# ETAG.net
KiCad netlist of a schematic drawn in EAGLE
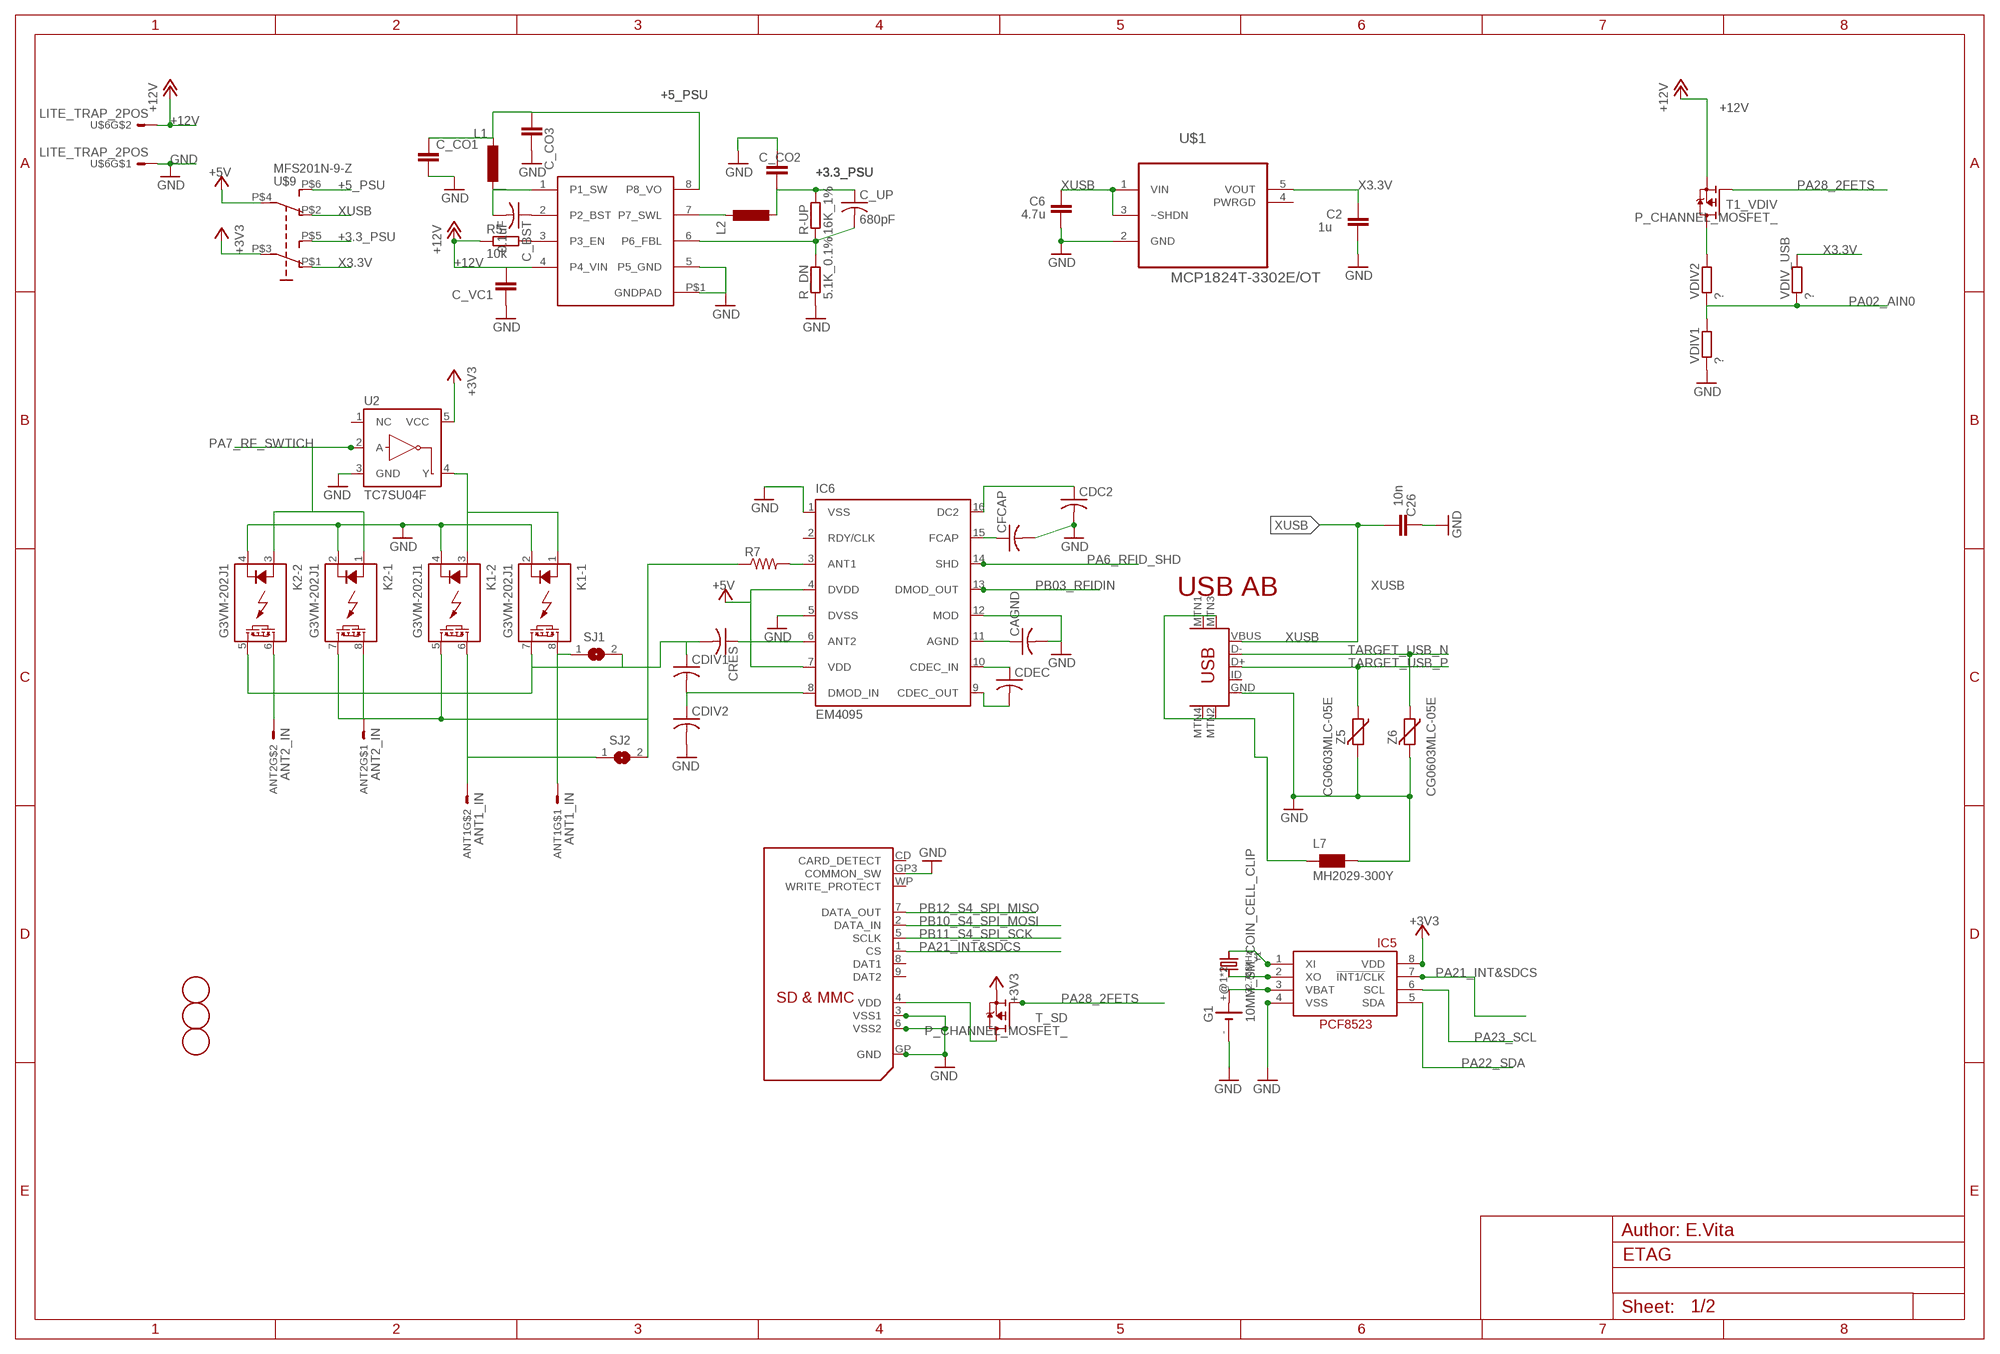
[diagram p0: schematic, sheet 1]
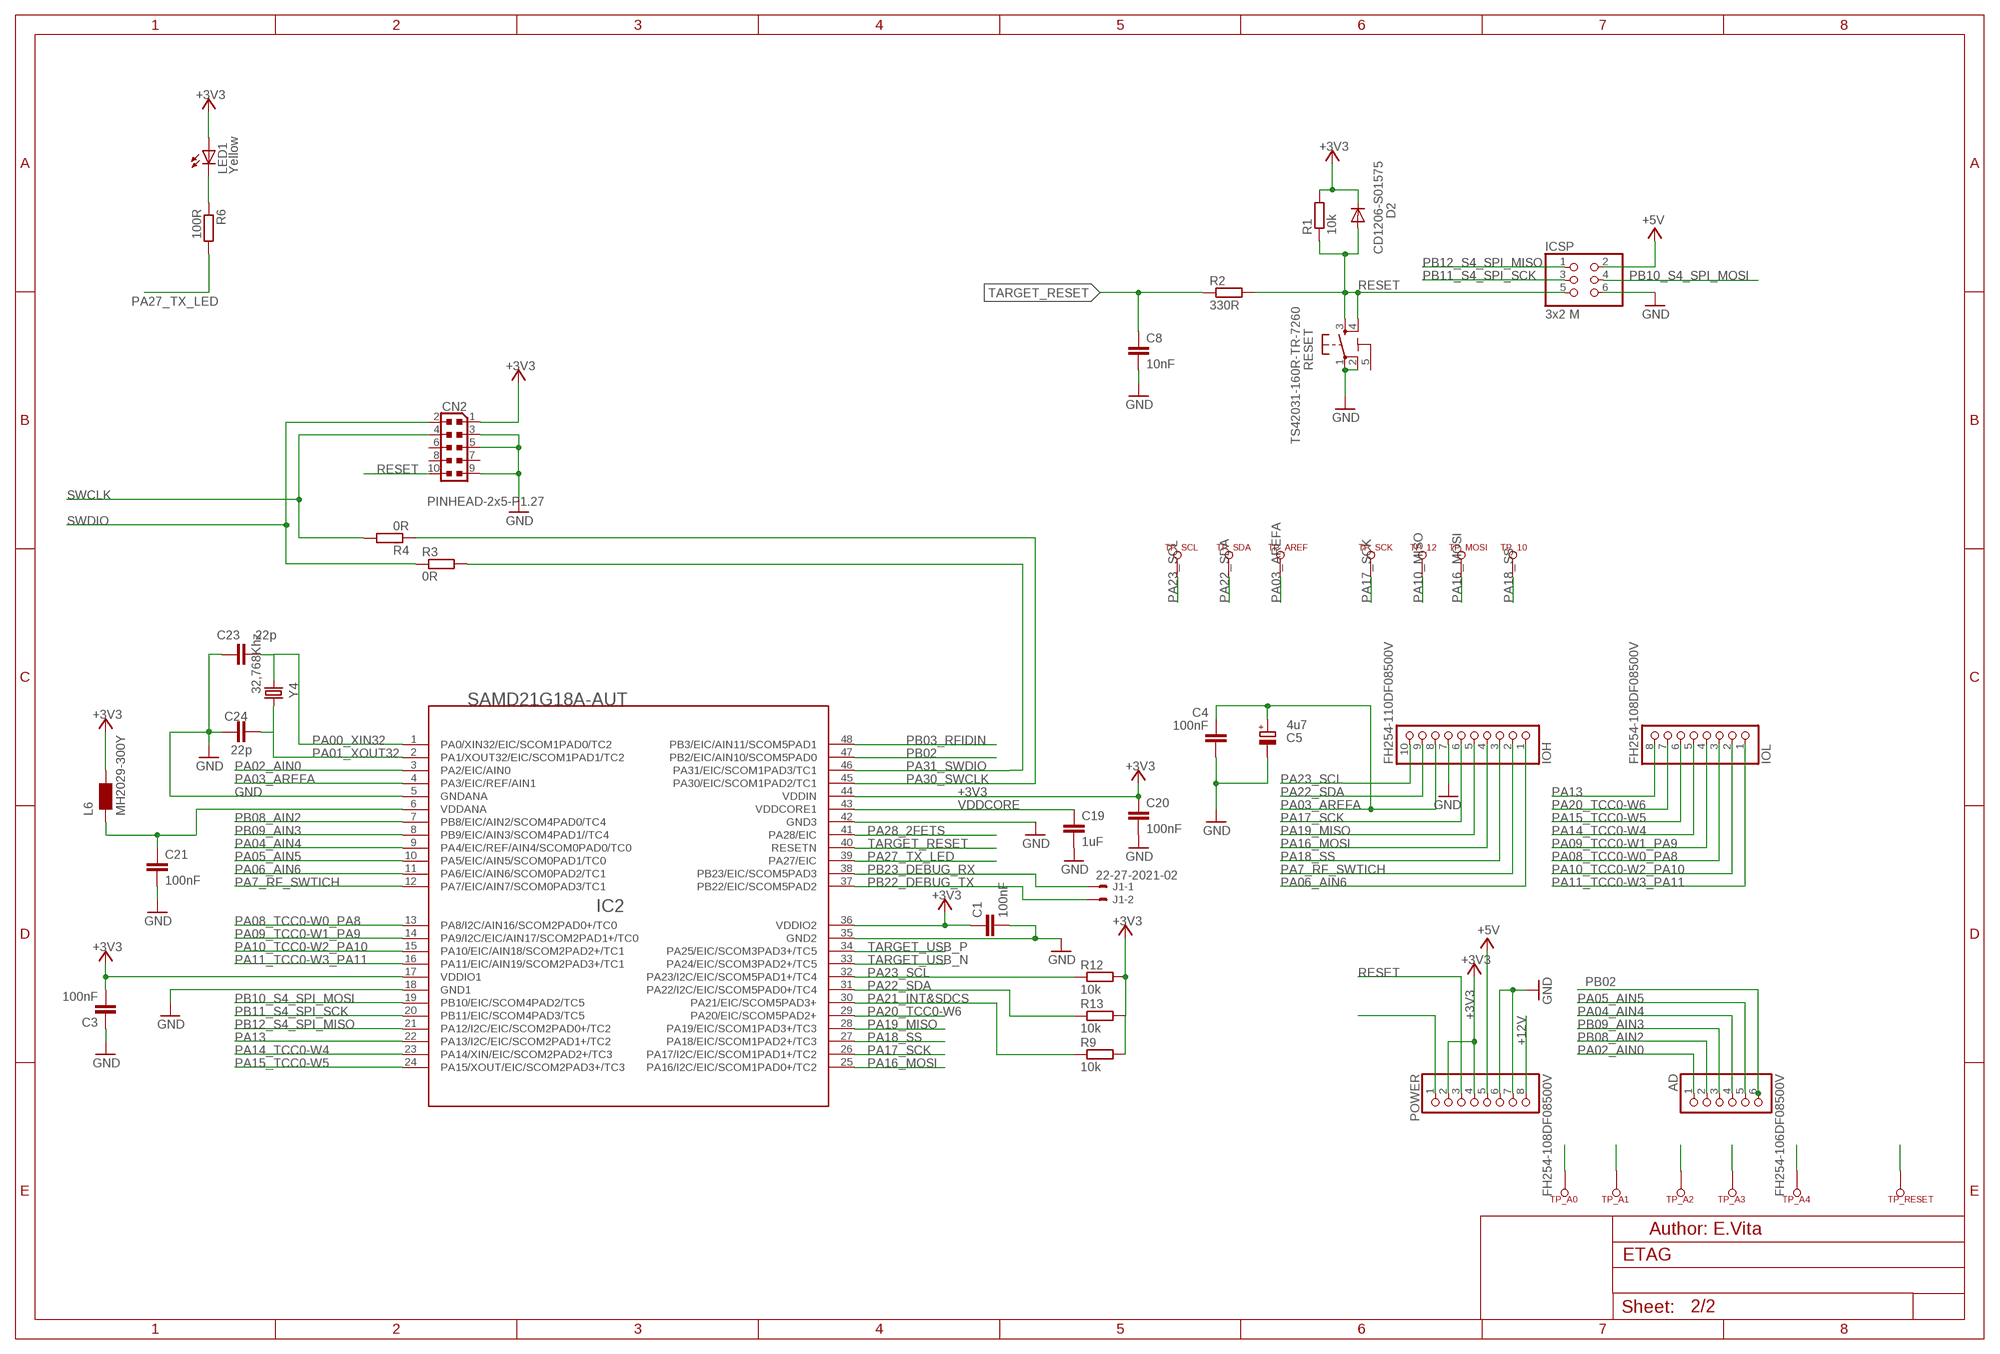
[diagram p1: schematic, sheet 2]

(export (version "E")
  (design (tool "Eeschema 10.0.6"))
  (components
    (comp (ref "AD")
      (value "FH254-106DF08500V")
      (footprint "eagle-import:1X06")
      (fields (field (name "PART_NUMBER") "20TW-535"))
      (libsource (lib "eagle-import") (part "1682_20TW-535_STD"))
    )
    (comp (ref "C1")
      (value "100nF")
      (footprint "eagle-import:C0603-ROUND")
      (fields (field (name "PART_NUMBER") "cl10b104kbnc"))
      (libsource (lib "eagle-import") (part "0015_100NF_0603"))
    )
    (comp (ref "C3")
      (value "100nF")
      (footprint "eagle-import:C0603-ROUND")
      (fields (field (name "PART_NUMBER") "cl10b104kbnc"))
      (libsource (lib "eagle-import") (part "0015_100NF_0603"))
    )
    (comp (ref "C4")
      (value "100nF")
      (footprint "eagle-import:C0603-ROUND")
      (fields (field (name "PART_NUMBER") "cl10b104kbnc"))
      (libsource (lib "eagle-import") (part "0015_100NF_0603"))
    )
    (comp (ref "C5")
      (value "4u7")
      (footprint "eagle-import:SMC_A")
      (fields (field (name "PART_NUMBER") "TAJA475M016RNJ"))
      (libsource (lib "eagle-import") (part "0474_TAJA475M016RNJ"))
    )
    (comp (ref "C8")
      (value "10nF")
      (footprint "eagle-import:C0603-ROUND")
      (fields (field (name "PART_NUMBER") "10nF_0603"))
      (libsource (lib "eagle-import") (part "0142_10NF_0603"))
    )
    (comp (ref "C19")
      (value "1uF")
      (footprint "eagle-import:C0603-ROUND")
      (fields (field (name "PART_NUMBER") "1uF_0603/GRM188R61E105KA12D"))
      (libsource (lib "eagle-import") (part "0006_1UF_0603/GRM188R61E105KA12D"))
    )
    (comp (ref "C20")
      (value "100nF")
      (footprint "eagle-import:C0603-ROUND")
      (fields (field (name "PART_NUMBER") "cl10b104kbnc"))
      (libsource (lib "eagle-import") (part "0015_100NF_0603"))
    )
    (comp (ref "C21")
      (value "100nF")
      (footprint "eagle-import:C0603-ROUND")
      (fields (field (name "PART_NUMBER") "cl10b104kbnc"))
      (libsource (lib "eagle-import") (part "0015_100NF_0603"))
    )
    (comp (ref "C23")
      (value "22p")
      (footprint "eagle-import:C0603-ROUND")
      (fields (field (name "PART_NUMBER") "22pF_0603"))
      (libsource (lib "eagle-import") (part "0014_22PF_0603"))
    )
    (comp (ref "C24")
      (value "22p")
      (footprint "eagle-import:C0603-ROUND")
      (fields (field (name "PART_NUMBER") "22pF_0603"))
      (libsource (lib "eagle-import") (part "0014_22PF_0603"))
    )
    (comp (ref "CN2")
      (value "PINHEAD-2x5-P1.27")
      (footprint "eagle-import:PINHEAD_2X05_127")
      (libsource (lib "eagle-import") (part "0171_PH127-205DF055G00AROUND-PADS"))
    )
    (comp (ref "D2")
      (value "CD1206-S01575")
      (footprint "eagle-import:MINIMELF")
      (libsource (lib "eagle-import") (part "0012_CD1206-S01575"))
    )
    (comp (ref "IC2")
      (value "SAMD21G18A-AUT")
      (footprint "eagle-import:TQFP48-7X7")
      (libsource (lib "eagle-import") (part "1792_SAMD21G18A-AUT"))
    )
    (comp (ref "ICSP")
      (value "3x2 M")
      (footprint "eagle-import:2X03")
      (fields (field (name "PART_NUMBER") "PH254-203DF118A00V"))
      (libsource (lib "eagle-import") (part "0114_PH254-203DF118A00V"))
    )
    (comp (ref "IOH")
      (value "FH254-110DF08500V")
      (footprint "eagle-import:1X10")
      (fields (field (name "PART_NUMBER") "20TW-537"))
      (libsource (lib "eagle-import") (part "1684_20TW-537"))
    )
    (comp (ref "IOL")
      (value "FH254-108DF08500V")
      (footprint "eagle-import:1X08")
      (fields (field (name "PART_NUMBER") "20TW-536"))
      (libsource (lib "eagle-import") (part "1683_20TW-536"))
    )
    (comp (ref "J1")
      (value "22-27-2021-02")
      (footprint "eagle-import:6410-02")
      (libsource (lib "eagle-import") (part "22-?-0227-2021"))
    )
    (comp (ref "L6")
      (value "MH2029-300Y")
      (footprint "eagle-import:0805")
      (fields (field (name "PART_NUMBER") "BLM21PG300SN1D_/_MH2029-300Y"))
      (libsource (lib "eagle-import") (part "0001_BLM21PG300SN1D_/_MH2029-300Y"))
    )
    (comp (ref "LED1")
      (value "Yellow")
      (footprint "eagle-import:CHIPLED_0805")
      (fields (field (name "PART_NUMBER") "KPT-2012YC"))
      (libsource (lib "eagle-import") (part "0044_KPT-2012YC"))
    )
    (comp (ref "POWER")
      (value "FH254-108DF08500V")
      (footprint "eagle-import:1X08")
      (fields (field (name "PART_NUMBER") "20TW-536"))
      (libsource (lib "eagle-import") (part "1683_20TW-536"))
    )
    (comp (ref "R1")
      (value "10k")
      (footprint "eagle-import:R0603-ROUND")
      (fields (field (name "PART_NUMBER") "CR0603JW103L"))
      (libsource (lib "eagle-import") (part "0028_CR0603JW103L"))
    )
    (comp (ref "R2")
      (value "330R")
      (footprint "eagle-import:R0603-ROUND")
      (fields (field (name "PART_NUMBER") "330R_0603"))
      (libsource (lib "eagle-import") (part "0049_330R_0603"))
    )
    (comp (ref "R3")
      (value "0R")
      (footprint "eagle-import:R0603-ROUND")
      (fields (field (name "PART_NUMBER") "0R_0603"))
      (libsource (lib "eagle-import") (part "0233_0R_0603"))
    )
    (comp (ref "R4")
      (value "0R")
      (footprint "eagle-import:R0603-ROUND")
      (fields (field (name "PART_NUMBER") "0R_0603"))
      (libsource (lib "eagle-import") (part "0233_0R_0603"))
    )
    (comp (ref "R6")
      (value "100R")
      (footprint "eagle-import:R0603-ROUND")
      (fields (field (name "PART_NUMBER") "0R_0603"))
      (libsource (lib "eagle-import") (part "0233_0R_0603"))
    )
    (comp (ref "R9")
      (value "10k")
      (footprint "eagle-import:R0603-ROUND")
      (fields (field (name "PART_NUMBER") "CR0603JW103L"))
      (libsource (lib "eagle-import") (part "0028_CR0603JW103L"))
    )
    (comp (ref "R12")
      (value "10k")
      (footprint "eagle-import:R0603-ROUND")
      (fields (field (name "PART_NUMBER") "CR0603JW103L"))
      (libsource (lib "eagle-import") (part "0028_CR0603JW103L"))
    )
    (comp (ref "R13")
      (value "10k")
      (footprint "eagle-import:R0603-ROUND")
      (fields (field (name "PART_NUMBER") "CR0603JW103L"))
      (libsource (lib "eagle-import") (part "0028_CR0603JW103L"))
    )
    (comp (ref "RESET")
      (value "TS42031-160R-TR-7260")
      (footprint "eagle-import:TS42")
      (fields (field (name "PART_NUMBER") "IT-1157AHNP-160G-G_GTR"))
      (libsource (lib "eagle-import") (part "0946_TS42031-160W-TR-7260"))
    )
    (comp (ref "TP_10")
      (value "TP_SP")
      (footprint "eagle-import:TP-SP")
      (libsource (lib "eagle-import") (part "TP_SP"))
    )
    (comp (ref "TP_12")
      (value "TP_SP")
      (footprint "eagle-import:TP-SP")
      (libsource (lib "eagle-import") (part "TP_SP"))
    )
    (comp (ref "TP_A0")
      (value "TP_SP")
      (footprint "eagle-import:TP-SP")
      (libsource (lib "eagle-import") (part "TP_SP"))
    )
    (comp (ref "TP_A1")
      (value "TP_SP")
      (footprint "eagle-import:TP-SP")
      (libsource (lib "eagle-import") (part "TP_SP"))
    )
    (comp (ref "TP_A2")
      (value "TP_SP")
      (footprint "eagle-import:TP-SP")
      (libsource (lib "eagle-import") (part "TP_SP"))
    )
    (comp (ref "TP_A3")
      (value "TP_SP")
      (footprint "eagle-import:TP-SP")
      (libsource (lib "eagle-import") (part "TP_SP"))
    )
    (comp (ref "TP_A4")
      (value "TP_SP")
      (footprint "eagle-import:TP-SP")
      (libsource (lib "eagle-import") (part "TP_SP"))
    )
    (comp (ref "TP_AREF")
      (value "TP_SP")
      (footprint "eagle-import:TP-SP")
      (libsource (lib "eagle-import") (part "TP_SP"))
    )
    (comp (ref "TP_MOSI")
      (value "TP_SP")
      (footprint "eagle-import:TP-SP")
      (libsource (lib "eagle-import") (part "TP_SP"))
    )
    (comp (ref "TP_RESET")
      (value "TP_SP")
      (footprint "eagle-import:TP-SP")
      (libsource (lib "eagle-import") (part "TP_SP"))
    )
    (comp (ref "TP_SCK")
      (value "TP_SP")
      (footprint "eagle-import:TP-SP")
      (libsource (lib "eagle-import") (part "TP_SP"))
    )
    (comp (ref "TP_SCL")
      (value "TP_SP")
      (footprint "eagle-import:TP-SP")
      (libsource (lib "eagle-import") (part "TP_SP"))
    )
    (comp (ref "TP_SDA")
      (value "TP_SP")
      (footprint "eagle-import:TP-SP")
      (libsource (lib "eagle-import") (part "TP_SP"))
    )
    (comp (ref "Y4")
      (value "32,768Khz")
      (footprint "eagle-import:RESONATOR_EPSON_FC_145")
      (fields (field (name "PART_NUMBER") "ABS07-32.768KHZ-T"))
      (libsource (lib "eagle-import") (part "0213_ABS07-32.768KHZ-T"))
    )
    (comp (ref "ANT1")
      (value "ANT1_IN")
      (footprint "eagle-import:LITE_TRAP_MINI")
      (libsource (lib "eagle-import") (part "LITE_TRAP_2POS"))
    )
    (comp (ref "ANT2")
      (value "ANT2_IN")
      (footprint "eagle-import:LITE_TRAP_MINI")
      (libsource (lib "eagle-import") (part "LITE_TRAP_2POS"))
    )
    (comp (ref "C2")
      (value "1u")
      (footprint "eagle-import:C0603-ROUND")
      (fields (field (name "PART_NUMBER") "10nF_0603"))
      (libsource (lib "eagle-import") (part "0142_10NF_0603"))
    )
    (comp (ref "C6")
      (value "4.7u")
      (footprint "eagle-import:C0603-ROUND")
      (fields (field (name "PART_NUMBER") "10nF_0603"))
      (libsource (lib "eagle-import") (part "0142_10NF_0603"))
    )
    (comp (ref "C26")
      (value "10n")
      (footprint "eagle-import:C0603-ROUND")
      (fields (field (name "PART_NUMBER") "10nF_0603"))
      (libsource (lib "eagle-import") (part "0142_10NF_0603"))
    )
    (comp (ref "CAGND")
      (value "C-US")
      (footprint "eagle-import:C0603-ROUND")
      (libsource (lib "eagle-import") (part "C-US"))
    )
    (comp (ref "CDC2")
      (value "C-US")
      (footprint "eagle-import:C0603-ROUND")
      (libsource (lib "eagle-import") (part "C-US"))
    )
    (comp (ref "CDEC")
      (value "C-US")
      (footprint "eagle-import:C0603-ROUND")
      (libsource (lib "eagle-import") (part "C-US"))
    )
    (comp (ref "CDIV1")
      (value "C-USC1206K")
      (footprint "eagle-import:C1206K")
      (libsource (lib "eagle-import") (part "C-USC1206K"))
    )
    (comp (ref "CDIV2")
      (value "C-USC1206K")
      (footprint "eagle-import:C1206K")
      (libsource (lib "eagle-import") (part "C-USC1206K"))
    )
    (comp (ref "CFCAP")
      (value "C-US")
      (footprint "eagle-import:C0603-ROUND")
      (libsource (lib "eagle-import") (part "C-US"))
    )
    (comp (ref "CRES")
      (value "C-USC1206K")
      (footprint "eagle-import:C1206K")
      (libsource (lib "eagle-import") (part "C-USC1206K"))
    )
    (comp (ref "C_BST")
      (value "0.1uF")
      (footprint "eagle-import:C0603-ROUND")
      (libsource (lib "eagle-import") (part "C-US"))
    )
    (comp (ref "C_CO1")
      (value "22uF")
      (footprint "eagle-import:C0805")
      (libsource (lib "eagle-import") (part "C-EUC0805"))
    )
    (comp (ref "C_CO2")
      (value "22uF")
      (footprint "eagle-import:C0805")
      (libsource (lib "eagle-import") (part "C-EUC0805"))
    )
    (comp (ref "C_CO3")
      (value "10uF")
      (footprint "eagle-import:C0805")
      (libsource (lib "eagle-import") (part "C-EUC0805"))
    )
    (comp (ref "C_UP")
      (value "680pF")
      (footprint "eagle-import:C0603-ROUND")
      (libsource (lib "eagle-import") (part "C-US"))
    )
    (comp (ref "C_VC1")
      (value "10uF")
      (footprint "eagle-import:C1210")
      (libsource (lib "eagle-import") (part "C-EUC1210"))
    )
    (comp (ref "FD1")
      (value "FIDUCIALMOUNT")
      (footprint "eagle-import:FIDUCIA-MOUNT")
      (libsource (lib "eagle-import") (part "FIDUCIALMOUNT"))
    )
    (comp (ref "FD2")
      (value "FIDUCIALMOUNT")
      (footprint "eagle-import:FIDUCIA-MOUNT")
      (libsource (lib "eagle-import") (part "FIDUCIALMOUNT"))
    )
    (comp (ref "FD3")
      (value "FIDUCIALMOUNT")
      (footprint "eagle-import:FIDUCIA-MOUNT")
      (libsource (lib "eagle-import") (part "FIDUCIALMOUNT"))
    )
    (comp (ref "G1")
      (value "10MM_SM_COIN_CELL_CLIP")
      (footprint "eagle-import:10MM_SM_COIN_CELL_CLIP")
      (libsource (lib "eagle-import") (part "10MM_SM_COIN_CELL_CLIP"))
    )
    (comp (ref "IC5")
      (value "RTC_PCF8523T")
      (footprint "eagle-import:SOIC8_150MIL")
      (libsource (lib "eagle-import") (part "RTC_PCF8523T"))
    )
    (comp (ref "IC6")
      (value "EM4095")
      (footprint "eagle-import:SO16")
      (libsource (lib "eagle-import") (part "EM4095"))
    )
    (comp (ref "K1")
      (value "G3VM-202J1")
      (footprint "eagle-import:SOP08")
      (libsource (lib "eagle-import") (part "AQWSOP21"))
    )
    (comp (ref "K2")
      (value "G3VM-202J1")
      (footprint "eagle-import:SOP08")
      (libsource (lib "eagle-import") (part "AQWSOP21"))
    )
    (comp (ref "L1")
      (value "22uH")
      (footprint "eagle-import:SLF10165")
      (libsource (lib "eagle-import") (part "L-EUSLF_10MM"))
    )
    (comp (ref "L2")
      (value "2.2uH")
      (footprint "eagle-import:L1008(2520METRIC)")
      (libsource (lib "eagle-import") (part "L-EU1008"))
    )
    (comp (ref "L7")
      (value "MH2029-300Y")
      (footprint "eagle-import:0805")
      (fields (field (name "PART_NUMBER") "BLM21PG300SN1D_/_MH2029-300Y"))
      (libsource (lib "eagle-import") (part "0001_BLM21PG300SN1D_/_MH2029-300Y"))
    )
    (comp (ref "R-UP")
      (value "16K_1%")
      (footprint "eagle-import:R0603-ROUND")
      (fields (field (name "PART_NUMBER") "CR0603FW104L"))
      (libsource (lib "eagle-import") (part "2022_CR0603FW104L"))
    )
    (comp (ref "R5")
      (value "10k")
      (footprint "eagle-import:R0603-ROUND")
      (fields (field (name "PART_NUMBER") "CR0603JW103L"))
      (libsource (lib "eagle-import") (part "0028_CR0603JW103L"))
    )
    (comp (ref "R7")
      (value "R-US_R1206")
      (footprint "eagle-import:R1206")
      (libsource (lib "eagle-import") (part "R-US_R1206"))
    )
    (comp (ref "R_DN")
      (value "5.1K_0.1%")
      (footprint "eagle-import:R0603-ROUND")
      (libsource (lib "eagle-import") (part "2339_"))
    )
    (comp (ref "SJ1")
      (value "SJW")
      (footprint "eagle-import:SJW")
      (libsource (lib "eagle-import") (part "SJW"))
    )
    (comp (ref "SJ2")
      (value "SJW")
      (footprint "eagle-import:SJW")
      (libsource (lib "eagle-import") (part "SJW"))
    )
    (comp (ref "T1_VDIV")
      (value "P_CHANNEL_MOSFET_")
      (footprint "eagle-import:SOT23")
      (libsource (lib "eagle-import") (part "P_CHANNEL_MOSFET_"))
    )
    (comp (ref "T_SD")
      (value "P_CHANNEL_MOSFET_")
      (footprint "eagle-import:SOT23")
      (libsource (lib "eagle-import") (part "P_CHANNEL_MOSFET_"))
    )
    (comp (ref "U$1")
      (value "MCP1824T-3302E/OT")
      (footprint "eagle-import:SOT95P270X145-5N")
      (libsource (lib "eagle-import") (part "MCP1824T-3302E/OT"))
    )
    (comp (ref "U$3")
      (value "BD93291EFJSOP8_W_GND")
      (footprint "eagle-import:SOP08_GNDPAD")
      (libsource (lib "eagle-import") (part "BD93291EFJSOP8_W_GND"))
    )
    (comp (ref "U$4")
      (value "SDMMC06132")
      (footprint "eagle-import:06132")
      (libsource (lib "eagle-import") (part "SDMMC06132"))
    )
    (comp (ref "U$5")
      (value "USB-MINIB-5PIN")
      (footprint "eagle-import:USB-MINIB")
      (libsource (lib "eagle-import") (part "USB-MINIB-5PIN"))
    )
    (comp (ref "U$6")
      (value "LITE_TRAP_2POS")
      (footprint "eagle-import:LITE_TRAP_MINI")
      (libsource (lib "eagle-import") (part "LITE_TRAP_2POS"))
    )
    (comp (ref "U$9")
      (value "MFS201N-9-Z")
      (footprint "eagle-import:MFS201N-9-Z")
      (libsource (lib "eagle-import") (part "MFS201N-9-Z"))
    )
    (comp (ref "U2")
      (value "TC7SU04F")
      (footprint "eagle-import:SOT23-5")
      (libsource (lib "eagle-import") (part "INVERTER_SOT23-5"))
    )
    (comp (ref "VDIV1")
      (value "?")
      (footprint "eagle-import:R0603-ROUND")
      (libsource (lib "eagle-import") (part "2339_"))
    )
    (comp (ref "VDIV2")
      (value "?")
      (footprint "eagle-import:R0603-ROUND")
      (fields (field (name "PART_NUMBER") "CR0603FW104L"))
      (libsource (lib "eagle-import") (part "2022_CR0603FW104L"))
    )
    (comp (ref "VDIV_USB")
      (value "?")
      (footprint "eagle-import:R0603-ROUND")
      (libsource (lib "eagle-import") (part "2339_"))
    )
    (comp (ref "Y1")
      (value "32.768kHz")
      (footprint "eagle-import:CRYSTAL_8X3.8")
      (libsource (lib "eagle-import") (part "CRYSTAL8.0X3.8"))
    )
    (comp (ref "Z5")
      (value "CG0603MLC-05E")
      (footprint "eagle-import:CT_CN0603")
      (fields (field (name "PART_NUMBER") "BRNCG0603MLC-05E"))
      (libsource (lib "eagle-import") (part "0010_BRNCG0603MLC-05E"))
    )
    (comp (ref "Z6")
      (value "CG0603MLC-05E")
      (footprint "eagle-import:CT_CN0603")
      (fields (field (name "PART_NUMBER") "BRNCG0603MLC-05E"))
      (libsource (lib "eagle-import") (part "0010_BRNCG0603MLC-05E"))
    )
  )
  (nets
    (net (code "1") (name "+3.3_PSU") (class "Default")
      (node (ref "C_CO2") (pin "2") (pinfunction "2_2") (pintype "passive"))
      (node (ref "C_UP") (pin "1") (pinfunction "1_1") (pintype "passive"))
      (node (ref "L2") (pin "2") (pinfunction "2_2") (pintype "passive"))
      (node (ref "R-UP") (pin "2") (pinfunction "2_2") (pintype "passive"))
      (node (ref "U$9") (pin "P$5") (pinfunction "S_P$5") (pintype "passive"))
    )
    (net (code "2") (name "+3V3") (class "Default")
      (node (ref "C1") (pin "1") (pinfunction "1_1") (pintype "passive"))
      (node (ref "C20") (pin "1") (pinfunction "1_1") (pintype "passive"))
      (node (ref "C3") (pin "2") (pinfunction "2_2") (pintype "passive"))
      (node (ref "CN2") (pin "1") (pinfunction "1_1") (pintype "passive"))
      (node (ref "D2") (pin "C") (pinfunction "C_C") (pintype "passive"))
      (node (ref "IC2") (pin "17") (pinfunction "VDDIO1_17") (pintype "power_in"))
      (node (ref "IC2") (pin "36") (pinfunction "VDDIO2_36") (pintype "power_in"))
      (node (ref "IC2") (pin "44") (pinfunction "VDDIN_44") (pintype "power_in"))
      (node (ref "IC5") (pin "8") (pinfunction "VDD_8") (pintype "power_in"))
      (node (ref "L6") (pin "2") (pinfunction "2_2") (pintype "passive"))
      (node (ref "LED1") (pin "A") (pinfunction "A_A") (pintype "passive"))
      (node (ref "POWER") (pin "2") (pinfunction "2_2") (pintype "passive"))
      (node (ref "POWER") (pin "4") (pinfunction "4_4") (pintype "passive"))
      (node (ref "R1") (pin "2") (pinfunction "2_2") (pintype "passive"))
      (node (ref "R12") (pin "2") (pinfunction "2_2") (pintype "passive"))
      (node (ref "R13") (pin "2") (pinfunction "2_2") (pintype "passive"))
      (node (ref "R9") (pin "2") (pinfunction "2_2") (pintype "passive"))
      (node (ref "T_SD") (pin "2") (pinfunction "S_2") (pintype "passive"))
      (node (ref "U$9") (pin "P$3") (pinfunction "P_P$3") (pintype "passive"))
      (node (ref "U2") (pin "5") (pinfunction "VCC_5") (pintype "bidirectional"))
    )
    (net (code "3") (name "+5V") (class "Default")
      (node (ref "IC6") (pin "4") (pinfunction "DVDD_4") (pintype "power_in"))
      (node (ref "IC6") (pin "7") (pinfunction "VDD_7") (pintype "power_in"))
      (node (ref "ICSP") (pin "2") (pinfunction "2_2") (pintype "passive"))
      (node (ref "POWER") (pin "5") (pinfunction "5_5") (pintype "passive"))
      (node (ref "U$9") (pin "P$4") (pinfunction "P1_P$4") (pintype "passive"))
    )
    (net (code "4") (name "+5_PSU") (class "Default")
      (node (ref "C_CO1") (pin "1") (pinfunction "1_1") (pintype "passive"))
      (node (ref "C_CO3") (pin "1") (pinfunction "1_1") (pintype "passive"))
      (node (ref "L1") (pin "P$1") (pinfunction "1_P$1") (pintype "passive"))
      (node (ref "U$3") (pin "8") (pinfunction "P8_VO_8") (pintype "bidirectional"))
      (node (ref "U$9") (pin "P$6") (pinfunction "S1_P$6") (pintype "passive"))
    )
    (net (code "5") (name "+12V") (class "Default")
      (node (ref "C_VC1") (pin "2") (pinfunction "2_2") (pintype "passive"))
      (node (ref "POWER") (pin "8") (pinfunction "8_8") (pintype "passive"))
      (node (ref "R5") (pin "1") (pinfunction "1_1") (pintype "passive"))
      (node (ref "T1_VDIV") (pin "2") (pinfunction "S_2") (pintype "passive"))
      (node (ref "U$3") (pin "4") (pinfunction "P4_VIN_4") (pintype "bidirectional"))
      (node (ref "U$6") (pin "P$3") (pinfunction "S_P$3") (pintype "passive"))
      (node (ref "U$6") (pin "P$4") (pinfunction "S_P$4") (pintype "passive"))
    )
    (net (code "6") (name "5-GND") (class "Default")
      (node (ref "RESET") (pin "5") (pinfunction "5-GND_5") (pintype "power_in"))
    )
    (net (code "7") (name "GND") (class "Default")
      (node (ref "C1") (pin "2") (pinfunction "2_2") (pintype "passive"))
      (node (ref "C19") (pin "2") (pinfunction "2_2") (pintype "passive"))
      (node (ref "C2") (pin "1") (pinfunction "1_1") (pintype "passive"))
      (node (ref "C20") (pin "2") (pinfunction "2_2") (pintype "passive"))
      (node (ref "C21") (pin "2") (pinfunction "2_2") (pintype "passive"))
      (node (ref "C23") (pin "1") (pinfunction "1_1") (pintype "passive"))
      (node (ref "C24") (pin "1") (pinfunction "1_1") (pintype "passive"))
      (node (ref "C26") (pin "2") (pinfunction "2_2") (pintype "passive"))
      (node (ref "C3") (pin "1") (pinfunction "1_1") (pintype "passive"))
      (node (ref "C4") (pin "2") (pinfunction "2_2") (pintype "passive"))
      (node (ref "C5") (pin "-") (pinfunction "-_-") (pintype "passive"))
      (node (ref "C6") (pin "1") (pinfunction "1_1") (pintype "passive"))
      (node (ref "C8") (pin "2") (pinfunction "2_2") (pintype "passive"))
      (node (ref "CAGND") (pin "2") (pinfunction "2_2") (pintype "passive"))
      (node (ref "CDC2") (pin "2") (pinfunction "2_2") (pintype "passive"))
      (node (ref "CDIV2") (pin "2") (pinfunction "2_2") (pintype "passive"))
      (node (ref "CFCAP") (pin "2") (pinfunction "2_2") (pintype "passive"))
      (node (ref "CN2") (pin "3") (pinfunction "3_3") (pintype "passive"))
      (node (ref "CN2") (pin "5") (pinfunction "5_5") (pintype "passive"))
      (node (ref "CN2") (pin "9") (pinfunction "9_9") (pintype "passive"))
      (node (ref "C_CO1") (pin "2") (pinfunction "2_2") (pintype "passive"))
      (node (ref "C_CO2") (pin "1") (pinfunction "1_1") (pintype "passive"))
      (node (ref "C_CO3") (pin "2") (pinfunction "2_2") (pintype "passive"))
      (node (ref "C_VC1") (pin "1") (pinfunction "1_1") (pintype "passive"))
      (node (ref "G1") (pin "-") (pinfunction "-_-") (pintype "passive"))
      (node (ref "IC2") (pin "18") (pinfunction "GND1_18") (pintype "power_in"))
      (node (ref "IC2") (pin "35") (pinfunction "GND2_35") (pintype "power_in"))
      (node (ref "IC2") (pin "42") (pinfunction "GND3_42") (pintype "power_in"))
      (node (ref "IC2") (pin "5") (pinfunction "GNDANA_5") (pintype "power_in"))
      (node (ref "IC5") (pin "4") (pinfunction "VSS_4") (pintype "power_in"))
      (node (ref "IC6") (pin "1") (pinfunction "VSS_1") (pintype "power_in"))
      (node (ref "IC6") (pin "12") (pinfunction "MOD_12") (pintype "input"))
      (node (ref "IC6") (pin "5") (pinfunction "DVSS_5") (pintype "power_in"))
      (node (ref "ICSP") (pin "6") (pinfunction "6_6") (pintype "passive"))
      (node (ref "IOH") (pin "7") (pinfunction "7_7") (pintype "passive"))
      (node (ref "K1") (pin "2") (pinfunction "K_2") (pintype "passive"))
      (node (ref "K1") (pin "4") (pinfunction "K_4") (pintype "passive"))
      (node (ref "K2") (pin "2") (pinfunction "K_2") (pintype "passive"))
      (node (ref "K2") (pin "4") (pinfunction "K_4") (pintype "passive"))
      (node (ref "L7") (pin "2") (pinfunction "2_2") (pintype "passive"))
      (node (ref "POWER") (pin "6") (pinfunction "6_6") (pintype "passive"))
      (node (ref "POWER") (pin "7") (pinfunction "7_7") (pintype "passive"))
      (node (ref "RESET") (pin "1") (pinfunction "1_1") (pintype "passive"))
      (node (ref "RESET") (pin "2") (pinfunction "2_2") (pintype "passive"))
      (node (ref "R_DN") (pin "1") (pinfunction "1_1") (pintype "passive"))
      (node (ref "U$1") (pin "2") (pinfunction "GND_2") (pintype "passive"))
      (node (ref "U$3") (pin "5") (pinfunction "P5_GND_5") (pintype "bidirectional"))
      (node (ref "U$3") (pin "P$1") (pinfunction "GNDPAD_P$1") (pintype "bidirectional"))
      (node (ref "U$4") (pin "3") (pinfunction "VSS1_3") (pintype "power_in"))
      (node (ref "U$4") (pin "6") (pinfunction "VSS2_6") (pintype "power_in"))
      (node (ref "U$4") (pin "GP") (pinfunction "GND_GP") (pintype "power_in"))
      (node (ref "U$4") (pin "GP3") (pinfunction "COMMON_SW_GP3") (pintype "passive"))
      (node (ref "U$5") (pin "GND") (pinfunction "GND_GND") (pintype "bidirectional"))
      (node (ref "U$6") (pin "P$1") (pinfunction "S_P$1") (pintype "passive"))
      (node (ref "U$6") (pin "P$2") (pinfunction "S_P$2") (pintype "passive"))
      (node (ref "U2") (pin "3") (pinfunction "GND_3") (pintype "bidirectional"))
      (node (ref "VDIV1") (pin "1") (pinfunction "1_1") (pintype "passive"))
      (node (ref "Z5") (pin "2") (pinfunction "2_2") (pintype "passive"))
      (node (ref "Z6") (pin "2") (pinfunction "2_2") (pintype "passive"))
    )
    (net (code "8") (name "Net-(IC2-VDDANA)") (class "Default")
      (node (ref "C21") (pin "1") (pinfunction "1_1") (pintype "passive"))
      (node (ref "IC2") (pin "6") (pinfunction "VDDANA_6") (pintype "power_in"))
      (node (ref "L6") (pin "1") (pinfunction "1_1") (pintype "passive"))
    )
    (net (code "9") (name "Net-(IC5-VBAT)") (class "Default")
      (node (ref "G1") (pin "+@1") (pinfunction "+_+@1") (pintype "passive"))
      (node (ref "G1") (pin "+@2") (pinfunction "+_+@2") (pintype "passive"))
      (node (ref "IC5") (pin "3") (pinfunction "VBAT_3") (pintype "power_in"))
    )
    (net (code "10") (name "Net-(IC5-XI)") (class "Default")
      (node (ref "IC5") (pin "1") (pinfunction "XI_1") (pintype "input"))
      (node (ref "Y1") (pin "P$1") (pinfunction "1_P$1") (pintype "passive"))
    )
    (net (code "11") (name "Net-(IC5-XO)") (class "Default")
      (node (ref "IC5") (pin "2") (pinfunction "XO_2") (pintype "output"))
      (node (ref "Y1") (pin "P$4") (pinfunction "2_P$4") (pintype "passive"))
    )
    (net (code "12") (name "Net-(IC6-AGND)") (class "Default")
      (node (ref "CAGND") (pin "1") (pinfunction "1_1") (pintype "passive"))
      (node (ref "IC6") (pin "11") (pinfunction "AGND_11") (pintype "power_in"))
    )
    (net (code "13") (name "Net-(IC6-ANT1)") (class "Default")
      (node (ref "IC6") (pin "3") (pinfunction "ANT1_3") (pintype "passive"))
      (node (ref "R7") (pin "2") (pinfunction "2_2") (pintype "passive"))
    )
    (net (code "14") (name "Net-(IC6-ANT2)") (class "Default")
      (node (ref "CRES") (pin "1") (pinfunction "1_1") (pintype "passive"))
      (node (ref "IC6") (pin "6") (pinfunction "ANT2_6") (pintype "passive"))
    )
    (net (code "15") (name "Net-(IC6-CDEC_IN)") (class "Default")
      (node (ref "CDEC") (pin "1") (pinfunction "1_1") (pintype "passive"))
      (node (ref "IC6") (pin "10") (pinfunction "CDEC_IN_10") (pintype "input"))
    )
    (net (code "16") (name "Net-(IC6-CDEC_OUT)") (class "Default")
      (node (ref "CDEC") (pin "2") (pinfunction "2_2") (pintype "passive"))
      (node (ref "IC6") (pin "9") (pinfunction "CDEC_OUT_9") (pintype "output"))
    )
    (net (code "17") (name "Net-(IC6-DC2)") (class "Default")
      (node (ref "CDC2") (pin "1") (pinfunction "1_1") (pintype "passive"))
      (node (ref "IC6") (pin "16") (pinfunction "DC2_16") (pintype "passive"))
    )
    (net (code "18") (name "Net-(IC6-DMOD_IN)") (class "Default")
      (node (ref "CDIV1") (pin "2") (pinfunction "2_2") (pintype "passive"))
      (node (ref "CDIV2") (pin "1") (pinfunction "1_1") (pintype "passive"))
      (node (ref "IC6") (pin "8") (pinfunction "DMOD_IN_8") (pintype "input"))
    )
    (net (code "19") (name "Net-(IC6-FCAP)") (class "Default")
      (node (ref "CFCAP") (pin "1") (pinfunction "1_1") (pintype "passive"))
      (node (ref "IC6") (pin "15") (pinfunction "FCAP_15") (pintype "passive"))
    )
    (net (code "20") (name "Net-(K1A-A)") (class "Default")
      (node (ref "K1") (pin "1") (pinfunction "A_1") (pintype "passive"))
      (node (ref "K1") (pin "3") (pinfunction "A_3") (pintype "passive"))
      (node (ref "U2") (pin "4") (pinfunction "Y_4") (pintype "bidirectional"))
    )
    (net (code "21") (name "Net-(K1A-D1)") (class "Default")
      (node (ref "ANT1") (pin "P$1") (pinfunction "S_P$1") (pintype "passive"))
      (node (ref "ANT1") (pin "P$2") (pinfunction "S_P$2") (pintype "passive"))
      (node (ref "K1") (pin "8") (pinfunction "D1_8") (pintype "passive"))
      (node (ref "SJ1") (pin "1") (pinfunction "1_1") (pintype "passive"))
    )
    (net (code "22") (name "Net-(K1A-D2)") (class "Default")
      (node (ref "CDIV1") (pin "1") (pinfunction "1_1") (pintype "passive"))
      (node (ref "CRES") (pin "2") (pinfunction "2_2") (pintype "passive"))
      (node (ref "K1") (pin "7") (pinfunction "D2_7") (pintype "passive"))
      (node (ref "K2") (pin "5") (pinfunction "D2_5") (pintype "passive"))
      (node (ref "SJ1") (pin "2") (pinfunction "2_2") (pintype "passive"))
    )
    (net (code "23") (name "Net-(K1B-D1)") (class "Default")
      (node (ref "ANT1") (pin "P$3") (pinfunction "S_P$3") (pintype "passive"))
      (node (ref "ANT1") (pin "P$4") (pinfunction "S_P$4") (pintype "passive"))
      (node (ref "K1") (pin "6") (pinfunction "D1_6") (pintype "passive"))
      (node (ref "SJ2") (pin "1") (pinfunction "1_1") (pintype "passive"))
    )
    (net (code "24") (name "Net-(K1B-D2)") (class "Default")
      (node (ref "K1") (pin "5") (pinfunction "D2_5") (pintype "passive"))
      (node (ref "K2") (pin "7") (pinfunction "D2_7") (pintype "passive"))
      (node (ref "R7") (pin "1") (pinfunction "1_1") (pintype "passive"))
      (node (ref "SJ2") (pin "2") (pinfunction "2_2") (pintype "passive"))
    )
    (net (code "25") (name "Net-(K2A-D1)") (class "Default")
      (node (ref "ANT2") (pin "P$1") (pinfunction "S_P$1") (pintype "passive"))
      (node (ref "ANT2") (pin "P$2") (pinfunction "S_P$2") (pintype "passive"))
      (node (ref "K2") (pin "8") (pinfunction "D1_8") (pintype "passive"))
    )
    (net (code "26") (name "Net-(K2B-D1)") (class "Default")
      (node (ref "ANT2") (pin "P$3") (pinfunction "S_P$3") (pintype "passive"))
      (node (ref "ANT2") (pin "P$4") (pinfunction "S_P$4") (pintype "passive"))
      (node (ref "K2") (pin "6") (pinfunction "D1_6") (pintype "passive"))
    )
    (net (code "27") (name "Net-(L1-2)") (class "Default")
      (node (ref "C_BST") (pin "2") (pinfunction "2_2") (pintype "passive"))
      (node (ref "L1") (pin "P$2") (pinfunction "2_P$2") (pintype "passive"))
      (node (ref "U$3") (pin "1") (pinfunction "P1_SW_1") (pintype "bidirectional"))
    )
    (net (code "28") (name "Net-(LED1-PadC)") (class "Default")
      (node (ref "LED1") (pin "C") (pinfunction "C_C") (pintype "passive"))
      (node (ref "R6") (pin "1") (pinfunction "1_1") (pintype "passive"))
    )
    (net (code "29") (name "Net-(T1_VDIV-D)") (class "Default")
      (node (ref "T1_VDIV") (pin "3") (pinfunction "D_3") (pintype "passive"))
      (node (ref "VDIV2") (pin "2") (pinfunction "2_2") (pintype "passive"))
    )
    (net (code "30") (name "Net-(T_SD-D)") (class "Default")
      (node (ref "T_SD") (pin "3") (pinfunction "D_3") (pintype "passive"))
      (node (ref "U$4") (pin "4") (pinfunction "VDD_4") (pintype "power_in"))
    )
    (net (code "31") (name "Net-(U$3-P2_BST)") (class "Default")
      (node (ref "C_BST") (pin "1") (pinfunction "1_1") (pintype "passive"))
      (node (ref "U$3") (pin "2") (pinfunction "P2_BST_2") (pintype "bidirectional"))
    )
    (net (code "32") (name "Net-(U$3-P3_EN)") (class "Default")
      (node (ref "R5") (pin "2") (pinfunction "2_2") (pintype "passive"))
      (node (ref "U$3") (pin "3") (pinfunction "P3_EN_3") (pintype "bidirectional"))
    )
    (net (code "33") (name "Net-(U$3-P6_FBL)") (class "Default")
      (node (ref "C_UP") (pin "2") (pinfunction "2_2") (pintype "passive"))
      (node (ref "R-UP") (pin "1") (pinfunction "1_1") (pintype "passive"))
      (node (ref "R_DN") (pin "2") (pinfunction "2_2") (pintype "passive"))
      (node (ref "U$3") (pin "6") (pinfunction "P6_FBL_6") (pintype "bidirectional"))
    )
    (net (code "34") (name "Net-(U$3-P7_SWL)") (class "Default")
      (node (ref "L2") (pin "1") (pinfunction "1_1") (pintype "passive"))
      (node (ref "U$3") (pin "7") (pinfunction "P7_SWL_7") (pintype "bidirectional"))
    )
    (net (code "35") (name "Net-(U$5-MTN1)") (class "Default")
      (node (ref "L7") (pin "1") (pinfunction "1_1") (pintype "passive"))
      (node (ref "U$5") (pin "MTN1") (pinfunction "MTN2_MTN1") (pintype "bidirectional"))
      (node (ref "U$5") (pin "MTN2") (pinfunction "MTN3_MTN2") (pintype "bidirectional"))
      (node (ref "U$5") (pin "MTN3") (pinfunction "MTN1_MTN3") (pintype "bidirectional"))
      (node (ref "U$5") (pin "MTN4") (pinfunction "MTN4_MTN4") (pintype "bidirectional"))
    )
    (net (code "36") (name "PA00_XIN32") (class "Default")
      (node (ref "C23") (pin "2") (pinfunction "2_2") (pintype "passive"))
      (node (ref "IC2") (pin "1") (pinfunction "PA0/XIN32/EIC/SCOM1PAD0/TC2_1") (pintype "bidirectional"))
      (node (ref "Y4") (pin "P$1") (pinfunction "1_P$1") (pintype "bidirectional"))
    )
    (net (code "37") (name "PA01_XOUT32") (class "Default")
      (node (ref "C24") (pin "2") (pinfunction "2_2") (pintype "passive"))
      (node (ref "IC2") (pin "2") (pinfunction "PA1/XOUT32/EIC/SCOM1PAD1/TC2_2") (pintype "bidirectional"))
      (node (ref "Y4") (pin "P$2") (pinfunction "2_P$2") (pintype "bidirectional"))
    )
    (net (code "38") (name "PA02_AIN0") (class "Default")
      (node (ref "AD") (pin "1") (pinfunction "1_1") (pintype "passive"))
      (node (ref "IC2") (pin "3") (pinfunction "PA2/EIC/AIN0_3") (pintype "bidirectional"))
      (node (ref "TP_A0") (pin "X") (pinfunction "TESTP_X") (pintype "passive"))
      (node (ref "VDIV1") (pin "2") (pinfunction "2_2") (pintype "passive"))
      (node (ref "VDIV2") (pin "1") (pinfunction "1_1") (pintype "passive"))
      (node (ref "VDIV_USB") (pin "1") (pinfunction "1_1") (pintype "passive"))
    )
    (net (code "39") (name "PA03_AREFA") (class "Default")
      (node (ref "C4") (pin "1") (pinfunction "1_1") (pintype "passive"))
      (node (ref "C5") (pin "+") (pinfunction "+_+") (pintype "passive"))
      (node (ref "IC2") (pin "4") (pinfunction "PA3/EIC/REF/AIN1_4") (pintype "bidirectional"))
      (node (ref "IOH") (pin "8") (pinfunction "8_8") (pintype "passive"))
      (node (ref "TP_AREF") (pin "X") (pinfunction "TESTP_X") (pintype "passive"))
    )
    (net (code "40") (name "PA04_AIN4") (class "Default")
      (node (ref "AD") (pin "4") (pinfunction "4_4") (pintype "passive"))
      (node (ref "IC2") (pin "9") (pinfunction "PA4/EIC/REF/AIN4/SCOM0PAD0/TC0_9") (pintype "bidirectional"))
      (node (ref "TP_A3") (pin "X") (pinfunction "TESTP_X") (pintype "passive"))
    )
    (net (code "41") (name "PA05_AIN5") (class "Default")
      (node (ref "AD") (pin "5") (pinfunction "5_5") (pintype "passive"))
      (node (ref "IC2") (pin "10") (pinfunction "PA5/EIC/AIN5/SCOM0PAD1/TC0_10") (pintype "bidirectional"))
      (node (ref "TP_A4") (pin "X") (pinfunction "TESTP_X") (pintype "passive"))
    )
    (net (code "42") (name "PA06_AIN6") (class "Default")
      (node (ref "IC2") (pin "11") (pinfunction "PA6/EIC/AIN6/SCOM0PAD2/TC1_11") (pintype "bidirectional"))
      (node (ref "IOH") (pin "1") (pinfunction "1_1") (pintype "passive"))
    )
    (net (code "43") (name "PA6_RFID_SHD") (class "Default")
      (node (ref "IC6") (pin "14") (pinfunction "SHD_14") (pintype "input"))
    )
    (net (code "44") (name "PA7_RF_SWTICH") (class "Default")
      (node (ref "IC2") (pin "12") (pinfunction "PA7/EIC/AIN7/SCOM0PAD3/TC1_12") (pintype "bidirectional"))
      (node (ref "IOH") (pin "2") (pinfunction "2_2") (pintype "passive"))
      (node (ref "K2") (pin "1") (pinfunction "A_1") (pintype "passive"))
      (node (ref "K2") (pin "3") (pinfunction "A_3") (pintype "passive"))
      (node (ref "U2") (pin "2") (pinfunction "A_2") (pintype "bidirectional"))
    )
    (net (code "45") (name "PA08_TCC0-W0_PA8") (class "Default")
      (node (ref "IC2") (pin "13") (pinfunction "PA8/I2C/AIN16/SCOM2PAD0+/TC0_13") (pintype "bidirectional"))
      (node (ref "IOL") (pin "3") (pinfunction "3_3") (pintype "passive"))
    )
    (net (code "46") (name "PA09_TCC0-W1_PA9") (class "Default")
      (node (ref "IC2") (pin "14") (pinfunction "PA9/I2C/EIC/AIN17/SCOM2PAD1+/TC0_14") (pintype "bidirectional"))
      (node (ref "IOL") (pin "4") (pinfunction "4_4") (pintype "passive"))
    )
    (net (code "47") (name "PA10_MISO") (class "Default")
      (node (ref "TP_12") (pin "X") (pinfunction "TESTP_X") (pintype "passive"))
    )
    (net (code "48") (name "PA10_TCC0-W2_PA10") (class "Default")
      (node (ref "IC2") (pin "15") (pinfunction "PA10/EIC/AIN18/SCOM2PAD2+/TC1_15") (pintype "bidirectional"))
      (node (ref "IOL") (pin "2") (pinfunction "2_2") (pintype "passive"))
    )
    (net (code "49") (name "PA11_TCC0-W3_PA11") (class "Default")
      (node (ref "IC2") (pin "16") (pinfunction "PA11/EIC/AIN19/SCOM2PAD3+/TC1_16") (pintype "bidirectional"))
      (node (ref "IOL") (pin "1") (pinfunction "1_1") (pintype "passive"))
    )
    (net (code "50") (name "PA13") (class "Default")
      (node (ref "IC2") (pin "22") (pinfunction "PA13/I2C/EIC/SCOM2PAD1+/TC2_22") (pintype "bidirectional"))
      (node (ref "IOL") (pin "8") (pinfunction "8_8") (pintype "passive"))
    )
    (net (code "51") (name "PA14_TCC0-W4") (class "Default")
      (node (ref "IC2") (pin "23") (pinfunction "PA14/XIN/EIC/SCOM2PAD2+/TC3_23") (pintype "bidirectional"))
      (node (ref "IOL") (pin "5") (pinfunction "5_5") (pintype "passive"))
    )
    (net (code "52") (name "PA15_TCC0-W5") (class "Default")
      (node (ref "IC2") (pin "24") (pinfunction "PA15/XOUT/EIC/SCOM2PAD3+/TC3_24") (pintype "bidirectional"))
      (node (ref "IOL") (pin "6") (pinfunction "6_6") (pintype "passive"))
    )
    (net (code "53") (name "PA16_MOSI") (class "Default")
      (node (ref "IC2") (pin "25") (pinfunction "PA16/I2C/EIC/SCOM1PAD0+/TC2_25") (pintype "bidirectional"))
      (node (ref "IOH") (pin "4") (pinfunction "4_4") (pintype "passive"))
      (node (ref "TP_MOSI") (pin "X") (pinfunction "TESTP_X") (pintype "passive"))
    )
    (net (code "54") (name "PA17_SCK") (class "Default")
      (node (ref "IC2") (pin "26") (pinfunction "PA17/I2C/EIC/SCOM1PAD1+/TC2_26") (pintype "bidirectional"))
      (node (ref "IOH") (pin "6") (pinfunction "6_6") (pintype "passive"))
      (node (ref "TP_SCK") (pin "X") (pinfunction "TESTP_X") (pintype "passive"))
    )
    (net (code "55") (name "PA18_SS") (class "Default")
      (node (ref "IC2") (pin "27") (pinfunction "PA18/EIC/SCOM1PAD2+/TC3_27") (pintype "bidirectional"))
      (node (ref "IOH") (pin "3") (pinfunction "3_3") (pintype "passive"))
      (node (ref "TP_10") (pin "X") (pinfunction "TESTP_X") (pintype "passive"))
    )
    (net (code "56") (name "PA19_MISO") (class "Default")
      (node (ref "IC2") (pin "28") (pinfunction "PA19/EIC/SCOM1PAD3+/TC3_28") (pintype "bidirectional"))
      (node (ref "IOH") (pin "5") (pinfunction "5_5") (pintype "passive"))
    )
    (net (code "57") (name "PA20_TCC0-W6") (class "Default")
      (node (ref "IC2") (pin "29") (pinfunction "PA20/EIC/SCOM5PAD2+_29") (pintype "bidirectional"))
      (node (ref "IOL") (pin "7") (pinfunction "7_7") (pintype "passive"))
    )
    (net (code "58") (name "PA21_INT&SDCS") (class "Default")
      (node (ref "IC2") (pin "30") (pinfunction "PA21/EIC/SCOM5PAD3+_30") (pintype "bidirectional"))
      (node (ref "IC5") (pin "7") (pinfunction "~{INT1/CLK}_7") (pintype "output"))
      (node (ref "R9") (pin "1") (pinfunction "1_1") (pintype "passive"))
      (node (ref "U$4") (pin "1") (pinfunction "CS_1") (pintype "input"))
    )
    (net (code "59") (name "PA22_SDA") (class "Default")
      (node (ref "IC2") (pin "31") (pinfunction "PA22/I2C/EIC/SCOM5PAD0+/TC4_31") (pintype "bidirectional"))
      (node (ref "IC5") (pin "5") (pinfunction "SDA_5") (pintype "bidirectional"))
      (node (ref "IOH") (pin "9") (pinfunction "9_9") (pintype "passive"))
      (node (ref "R13") (pin "1") (pinfunction "1_1") (pintype "passive"))
      (node (ref "TP_SDA") (pin "X") (pinfunction "TESTP_X") (pintype "passive"))
    )
    (net (code "60") (name "PA23_SCL") (class "Default")
      (node (ref "IC2") (pin "32") (pinfunction "PA23/I2C/EIC/SCOM5PAD1+/TC4_32") (pintype "bidirectional"))
      (node (ref "IC5") (pin "6") (pinfunction "SCL_6") (pintype "bidirectional"))
      (node (ref "IOH") (pin "10") (pinfunction "10_10") (pintype "passive"))
      (node (ref "R12") (pin "1") (pinfunction "1_1") (pintype "passive"))
      (node (ref "TP_SCL") (pin "X") (pinfunction "TESTP_X") (pintype "passive"))
    )
    (net (code "61") (name "PA27_TX_LED") (class "Default")
      (node (ref "IC2") (pin "39") (pinfunction "PA27/EIC_39") (pintype "bidirectional"))
      (node (ref "R6") (pin "2") (pinfunction "2_2") (pintype "passive"))
    )
    (net (code "62") (name "PA28_2FETS") (class "Default")
      (node (ref "IC2") (pin "41") (pinfunction "PA28/EIC_41") (pintype "bidirectional"))
      (node (ref "T1_VDIV") (pin "1") (pinfunction "G_1") (pintype "passive"))
      (node (ref "T_SD") (pin "1") (pinfunction "G_1") (pintype "passive"))
    )
    (net (code "63") (name "PA30_SWCLK") (class "Default")
      (node (ref "IC2") (pin "45") (pinfunction "PA30/EIC/SCOM1PAD2/TC1_45") (pintype "bidirectional"))
      (node (ref "R4") (pin "1") (pinfunction "1_1") (pintype "passive"))
    )
    (net (code "64") (name "PA31_SWDIO") (class "Default")
      (node (ref "IC2") (pin "46") (pinfunction "PA31/EIC/SCOM1PAD3/TC1_46") (pintype "bidirectional"))
      (node (ref "R3") (pin "2") (pinfunction "2_2") (pintype "passive"))
    )
    (net (code "65") (name "PB02") (class "Default")
      (node (ref "AD") (pin "6") (pinfunction "6_6") (pintype "passive"))
      (node (ref "IC2") (pin "47") (pinfunction "PB2/EIC/AIN10/SCOM5PAD0_47") (pintype "bidirectional"))
    )
    (net (code "66") (name "PB03_RFIDIN") (class "Default")
      (node (ref "IC2") (pin "48") (pinfunction "PB3/EIC/AIN11/SCOM5PAD1_48") (pintype "bidirectional"))
      (node (ref "IC6") (pin "13") (pinfunction "DMOD_OUT_13") (pintype "output"))
    )
    (net (code "67") (name "PB08_AIN2") (class "Default")
      (node (ref "AD") (pin "2") (pinfunction "2_2") (pintype "passive"))
      (node (ref "IC2") (pin "7") (pinfunction "PB8/EIC/AIN2/SCOM4PAD0/TC4_7") (pintype "bidirectional"))
      (node (ref "TP_A1") (pin "X") (pinfunction "TESTP_X") (pintype "passive"))
    )
    (net (code "68") (name "PB09_AIN3") (class "Default")
      (node (ref "AD") (pin "3") (pinfunction "3_3") (pintype "passive"))
      (node (ref "IC2") (pin "8") (pinfunction "PB9/EIC/AIN3/SCOM4PAD1//TC4_8") (pintype "bidirectional"))
      (node (ref "TP_A2") (pin "X") (pinfunction "TESTP_X") (pintype "passive"))
    )
    (net (code "69") (name "PB10_S4_SPI_MOSI") (class "Default")
      (node (ref "IC2") (pin "19") (pinfunction "PB10/EIC/SCOM4PAD2/TC5_19") (pintype "bidirectional"))
      (node (ref "ICSP") (pin "4") (pinfunction "4_4") (pintype "passive"))
      (node (ref "U$4") (pin "2") (pinfunction "DATA_IN_2") (pintype "input"))
    )
    (net (code "70") (name "PB11_S4_SPI_SCK") (class "Default")
      (node (ref "IC2") (pin "20") (pinfunction "PB11/EIC/SCOM4PAD3/TC5_20") (pintype "bidirectional"))
      (node (ref "ICSP") (pin "3") (pinfunction "3_3") (pintype "passive"))
      (node (ref "U$4") (pin "5") (pinfunction "SCLK_5") (pintype "input"))
    )
    (net (code "71") (name "PB12_S4_SPI_MISO") (class "Default")
      (node (ref "IC2") (pin "21") (pinfunction "PA12/I2C/EIC/SCOM2PAD0+/TC2_21") (pintype "bidirectional"))
      (node (ref "ICSP") (pin "1") (pinfunction "1_1") (pintype "passive"))
      (node (ref "U$4") (pin "7") (pinfunction "DATA_OUT_7") (pintype "output"))
    )
    (net (code "72") (name "PB22_DEBUG_TX") (class "Default")
      (node (ref "IC2") (pin "37") (pinfunction "PB22/EIC/SCOM5PAD2_37") (pintype "bidirectional"))
      (node (ref "J1") (pin "2") (pinfunction "S_2") (pintype "passive"))
    )
    (net (code "73") (name "PB23_DEBUG_RX") (class "Default")
      (node (ref "IC2") (pin "38") (pinfunction "PB23/EIC/SCOM5PAD3_38") (pintype "bidirectional"))
      (node (ref "J1") (pin "1") (pinfunction "S_1") (pintype "passive"))
    )
    (net (code "74") (name "RESET") (class "Default")
      (node (ref "CN2") (pin "10") (pinfunction "10_10") (pintype "passive"))
      (node (ref "D2") (pin "A") (pinfunction "A_A") (pintype "passive"))
      (node (ref "ICSP") (pin "5") (pinfunction "5_5") (pintype "passive"))
      (node (ref "POWER") (pin "3") (pinfunction "3_3") (pintype "passive"))
      (node (ref "R1") (pin "1") (pinfunction "1_1") (pintype "passive"))
      (node (ref "R2") (pin "2") (pinfunction "2_2") (pintype "passive"))
      (node (ref "RESET") (pin "3") (pinfunction "3_3") (pintype "passive"))
      (node (ref "RESET") (pin "4") (pinfunction "4_4") (pintype "passive"))
      (node (ref "TP_RESET") (pin "X") (pinfunction "TESTP_X") (pintype "passive"))
    )
    (net (code "75") (name "SWCLK") (class "Default")
      (node (ref "CN2") (pin "4") (pinfunction "4_4") (pintype "passive"))
      (node (ref "R4") (pin "2") (pinfunction "2_2") (pintype "passive"))
    )
    (net (code "76") (name "SWDIO") (class "Default")
      (node (ref "CN2") (pin "2") (pinfunction "2_2") (pintype "passive"))
      (node (ref "R3") (pin "1") (pinfunction "1_1") (pintype "passive"))
    )
    (net (code "77") (name "TARGET_RESET") (class "Default")
      (node (ref "C8") (pin "1") (pinfunction "1_1") (pintype "passive"))
      (node (ref "IC2") (pin "40") (pinfunction "RESETN_40") (pintype "bidirectional"))
      (node (ref "R2") (pin "1") (pinfunction "1_1") (pintype "passive"))
    )
    (net (code "78") (name "TARGET_USB_N") (class "Default")
      (node (ref "IC2") (pin "33") (pinfunction "PA24/EIC/SCOM3PAD2+/TC5_33") (pintype "bidirectional"))
      (node (ref "U$5") (pin "D-") (pinfunction "D-_D-") (pintype "bidirectional"))
      (node (ref "Z6") (pin "1") (pinfunction "1_1") (pintype "passive"))
    )
    (net (code "79") (name "TARGET_USB_P") (class "Default")
      (node (ref "IC2") (pin "34") (pinfunction "PA25/EIC/SCOM3PAD3+/TC5_34") (pintype "bidirectional"))
      (node (ref "U$5") (pin "D+") (pinfunction "D+_D+") (pintype "bidirectional"))
      (node (ref "Z5") (pin "1") (pinfunction "1_1") (pintype "passive"))
    )
    (net (code "80") (name "VDDCORE") (class "Default")
      (node (ref "C19") (pin "1") (pinfunction "1_1") (pintype "passive"))
      (node (ref "IC2") (pin "43") (pinfunction "VDDCORE1_43") (pintype "input"))
    )
    (net (code "81") (name "X3.3V") (class "Default")
      (node (ref "C2") (pin "2") (pinfunction "2_2") (pintype "passive"))
      (node (ref "U$1") (pin "5") (pinfunction "VOUT_5") (pintype "output"))
      (node (ref "U$9") (pin "P$1") (pinfunction "O_P$1") (pintype "passive"))
      (node (ref "VDIV_USB") (pin "2") (pinfunction "2_2") (pintype "passive"))
    )
    (net (code "82") (name "XUSB") (class "Default")
      (node (ref "C26") (pin "1") (pinfunction "1_1") (pintype "passive"))
      (node (ref "C6") (pin "2") (pinfunction "2_2") (pintype "passive"))
      (node (ref "U$1") (pin "1") (pinfunction "VIN_1") (pintype "input"))
      (node (ref "U$1") (pin "3") (pinfunction "~{SHDN}_3") (pintype "input"))
      (node (ref "U$5") (pin "VBUS") (pinfunction "VBUS_VBUS") (pintype "bidirectional"))
      (node (ref "U$9") (pin "P$2") (pinfunction "O1_P$2") (pintype "passive"))
    )
    (net (code "83") (name "unconnected-(CN2-Pad6)") (class "Default")
      (node (ref "CN2") (pin "6") (pinfunction "6_6") (pintype "passive"))
    )
    (net (code "84") (name "unconnected-(CN2-Pad7)") (class "Default")
      (node (ref "CN2") (pin "7") (pinfunction "7_7") (pintype "passive"))
    )
    (net (code "85") (name "unconnected-(CN2-Pad8)") (class "Default")
      (node (ref "CN2") (pin "8") (pinfunction "8_8") (pintype "passive"))
    )
    (net (code "86") (name "unconnected-(IC6-RDY{slash}CLK-Pad2)") (class "Default")
      (node (ref "IC6") (pin "2") (pinfunction "RDY/CLK_2") (pintype "output"))
    )
    (net (code "87") (name "unconnected-(POWER-Pad1)") (class "Default")
      (node (ref "POWER") (pin "1") (pinfunction "1_1") (pintype "passive"))
    )
    (net (code "88") (name "unconnected-(U$1-PWRGD-Pad4)") (class "Default")
      (node (ref "U$1") (pin "4") (pinfunction "PWRGD_4") (pintype "output"))
    )
    (net (code "89") (name "unconnected-(U$4-CARD_DETECT-PadCD)") (class "Default")
      (node (ref "U$4") (pin "CD") (pinfunction "CARD_DETECT_CD") (pintype "passive"))
    )
    (net (code "90") (name "unconnected-(U$4-DAT1-Pad8)") (class "Default")
      (node (ref "U$4") (pin "8") (pinfunction "DAT1_8") (pintype "bidirectional"))
    )
    (net (code "91") (name "unconnected-(U$4-DAT2-Pad9)") (class "Default")
      (node (ref "U$4") (pin "9") (pinfunction "DAT2_9") (pintype "bidirectional"))
    )
    (net (code "92") (name "unconnected-(U$4-WRITE_PROTECT-PadWP)") (class "Default")
      (node (ref "U$4") (pin "WP") (pinfunction "WRITE_PROTECT_WP") (pintype "passive"))
    )
    (net (code "93") (name "unconnected-(U$5-PadID)") (class "Default")
      (node (ref "U$5") (pin "ID") (pinfunction "ID_ID") (pintype "bidirectional"))
    )
    (net (code "94") (name "unconnected-(U2-NC-Pad1)") (class "Default")
      (node (ref "U2") (pin "1") (pinfunction "NC_1") (pintype "bidirectional"))
    )
  )
)
